# sound-board.net
KiCad netlist of a schematic drawn in EAGLE
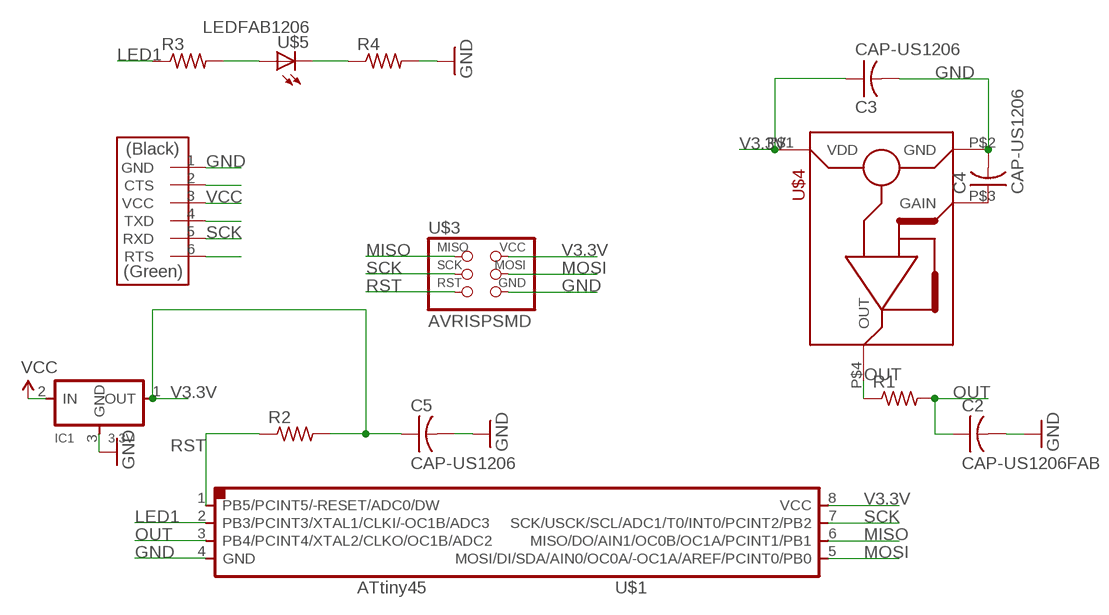
[diagram p0: schematic, sheet 1]

(export (version "E")
  (design (tool "Eeschema 10.0.6"))
  (components
    (comp (ref "C2")
      (value "CAP-US1206FAB")
      (footprint "eagle-import:C1206FAB")
      (libsource (lib "eagle-import") (part "CAP-US1206FAB"))
    )
    (comp (ref "C3")
      (value "CAP-US1206")
      (footprint "eagle-import:C1206")
      (libsource (lib "eagle-import") (part "CAP-US1206"))
    )
    (comp (ref "C4")
      (value "CAP-US1206")
      (footprint "eagle-import:C1206")
      (libsource (lib "eagle-import") (part "CAP-US1206"))
    )
    (comp (ref "C5")
      (value "CAP-US1206")
      (footprint "eagle-import:C1206")
      (libsource (lib "eagle-import") (part "CAP-US1206"))
    )
    (comp (ref "IC1")
      (value "3.3V")
      (footprint "eagle-import:SOT23")
      (libsource (lib "eagle-import") (part "REGULATORSOT23"))
    )
    (comp (ref "R1")
      (value "RES-US1206")
      (footprint "eagle-import:R1206")
      (libsource (lib "eagle-import") (part "RES-US1206"))
    )
    (comp (ref "R2")
      (value "RES-US1206")
      (footprint "eagle-import:R1206")
      (libsource (lib "eagle-import") (part "RES-US1206"))
    )
    (comp (ref "R3")
      (value "RES-US1206FAB")
      (footprint "eagle-import:R1206FAB")
      (libsource (lib "eagle-import") (part "RES-US1206FAB"))
    )
    (comp (ref "R4")
      (value "RES-US1206FAB")
      (footprint "eagle-import:R1206FAB")
      (libsource (lib "eagle-import") (part "RES-US1206FAB"))
    )
    (comp (ref "U$1")
      (value "ATTINY45SI")
      (footprint "eagle-import:SOIC8")
      (libsource (lib "eagle-import") (part "ATTINY45SI"))
    )
    (comp (ref "U$2")
      (value "FTDI-SMD-HEADER")
      (footprint "eagle-import:1X06SMD")
      (libsource (lib "eagle-import") (part "FTDI-SMD-HEADER"))
    )
    (comp (ref "U$3")
      (value "AVRISPSMD")
      (footprint "eagle-import:2X03SMD")
      (libsource (lib "eagle-import") (part "AVRISPSMD"))
    )
    (comp (ref "U$4")
      (value "MEMS_MIC_SPU0414HR5H-SB")
      (footprint "eagle-import:CSP-4PIN")
      (libsource (lib "eagle-import") (part "MEMS_MIC_SPU0414HR5H-SB"))
    )
    (comp (ref "U$5")
      (value "LEDFAB1206")
      (footprint "eagle-import:LED1206FAB")
      (libsource (lib "eagle-import") (part "LEDFAB1206"))
    )
  )
  (nets
    (net (code "1") (name "/LED1") (class "Default")
      (node (ref "R3") (pin "1") (pinfunction "1_1") (pintype "passive"))
      (node (ref "U$1") (pin "2") (pinfunction "PB3/PCINT3/XTAL1/CLKI/-OC1B/ADC3_2") (pintype "bidirectional"))
    )
    (net (code "2") (name "/MISO") (class "Default")
      (node (ref "U$1") (pin "6") (pinfunction "MISO/DO/AIN1/OC0B/OC1A/PCINT1/PB1_6") (pintype "bidirectional"))
      (node (ref "U$3") (pin "1") (pinfunction "MISO_1") (pintype "passive"))
    )
    (net (code "3") (name "/MOSI") (class "Default")
      (node (ref "U$1") (pin "5") (pinfunction "MOSI/DI/SDA/AIN0/OC0A/-OC1A/AREF/PCINT0/PB0_5") (pintype "bidirectional"))
      (node (ref "U$3") (pin "4") (pinfunction "MOSI_4") (pintype "passive"))
    )
    (net (code "4") (name "/OUT") (class "Default")
      (node (ref "C2") (pin "1") (pinfunction "1_1") (pintype "passive"))
      (node (ref "R1") (pin "1") (pinfunction "1_1") (pintype "passive"))
      (node (ref "R1") (pin "2") (pinfunction "2_2") (pintype "passive"))
      (node (ref "U$1") (pin "3") (pinfunction "PB4/PCINT4/XTAL2/CLKO/OC1B/ADC2_3") (pintype "bidirectional"))
      (node (ref "U$4") (pin "P$4") (pinfunction "OUT_P$4") (pintype "bidirectional"))
    )
    (net (code "5") (name "/RST") (class "Default")
      (node (ref "R2") (pin "1") (pinfunction "1_1") (pintype "passive"))
      (node (ref "U$1") (pin "1") (pinfunction "PB5/PCINT5/-RESET/ADC0/DW_1") (pintype "bidirectional"))
      (node (ref "U$3") (pin "5") (pinfunction "RST_5") (pintype "passive"))
    )
    (net (code "6") (name "/SCK") (class "Default")
      (node (ref "U$1") (pin "7") (pinfunction "SCK/USCK/SCL/ADC1/T0/INT0/PCINT2/PB2_7") (pintype "bidirectional"))
      (node (ref "U$2") (pin "5") (pinfunction "RXD_5") (pintype "bidirectional"))
      (node (ref "U$3") (pin "3") (pinfunction "SCK_3") (pintype "passive"))
    )
    (net (code "7") (name "/V3.3V") (class "Default")
      (node (ref "C3") (pin "1") (pinfunction "1_1") (pintype "passive"))
      (node (ref "C5") (pin "1") (pinfunction "1_1") (pintype "passive"))
      (node (ref "IC1") (pin "1") (pinfunction "OUT_1") (pintype "bidirectional"))
      (node (ref "R2") (pin "2") (pinfunction "2_2") (pintype "passive"))
      (node (ref "U$1") (pin "8") (pinfunction "VCC_8") (pintype "bidirectional"))
      (node (ref "U$3") (pin "2") (pinfunction "VCC_2") (pintype "passive"))
      (node (ref "U$4") (pin "P$1") (pinfunction "VDD_P$1") (pintype "bidirectional"))
    )
    (net (code "8") (name "GND") (class "Default")
      (node (ref "C2") (pin "2") (pinfunction "2_2") (pintype "passive"))
      (node (ref "C3") (pin "2") (pinfunction "2_2") (pintype "passive"))
      (node (ref "C4") (pin "2") (pinfunction "2_2") (pintype "passive"))
      (node (ref "C5") (pin "2") (pinfunction "2_2") (pintype "passive"))
      (node (ref "IC1") (pin "3") (pinfunction "GND_3") (pintype "bidirectional"))
      (node (ref "R4") (pin "2") (pinfunction "2_2") (pintype "passive"))
      (node (ref "U$1") (pin "4") (pinfunction "GND_4") (pintype "bidirectional"))
      (node (ref "U$2") (pin "1") (pinfunction "GND_1") (pintype "bidirectional"))
      (node (ref "U$3") (pin "6") (pinfunction "GND_6") (pintype "passive"))
      (node (ref "U$4") (pin "P$2") (pinfunction "GND_P$2") (pintype "bidirectional"))
    )
    (net (code "9") (name "Net-(U$4-GAIN)") (class "Default")
      (node (ref "C4") (pin "1") (pinfunction "1_1") (pintype "passive"))
      (node (ref "U$4") (pin "P$3") (pinfunction "GAIN_P$3") (pintype "bidirectional"))
    )
    (net (code "10") (name "Net-(U$5-A)") (class "Default")
      (node (ref "R3") (pin "2") (pinfunction "2_2") (pintype "passive"))
      (node (ref "U$5") (pin "1") (pinfunction "A_1") (pintype "passive"))
    )
    (net (code "11") (name "Net-(U$5-C)") (class "Default")
      (node (ref "R4") (pin "1") (pinfunction "1_1") (pintype "passive"))
      (node (ref "U$5") (pin "2") (pinfunction "C_2") (pintype "passive"))
    )
    (net (code "12") (name "VCC") (class "Default")
      (node (ref "IC1") (pin "2") (pinfunction "IN_2") (pintype "bidirectional"))
      (node (ref "U$2") (pin "3") (pinfunction "VCC_3") (pintype "bidirectional"))
    )
    (net (code "13") (name "unconnected-(U$2-CTS-Pad2)") (class "Default")
      (node (ref "U$2") (pin "2") (pinfunction "CTS_2") (pintype "bidirectional"))
    )
    (net (code "14") (name "unconnected-(U$2-RTS-Pad6)") (class "Default")
      (node (ref "U$2") (pin "6") (pinfunction "RTS_6") (pintype "bidirectional"))
    )
    (net (code "15") (name "unconnected-(U$2-TXD-Pad4)") (class "Default")
      (node (ref "U$2") (pin "4") (pinfunction "TXD_4") (pintype "bidirectional"))
    )
  )
)
